# satellitev2.net
KiCad netlist of a schematic drawn in EAGLE
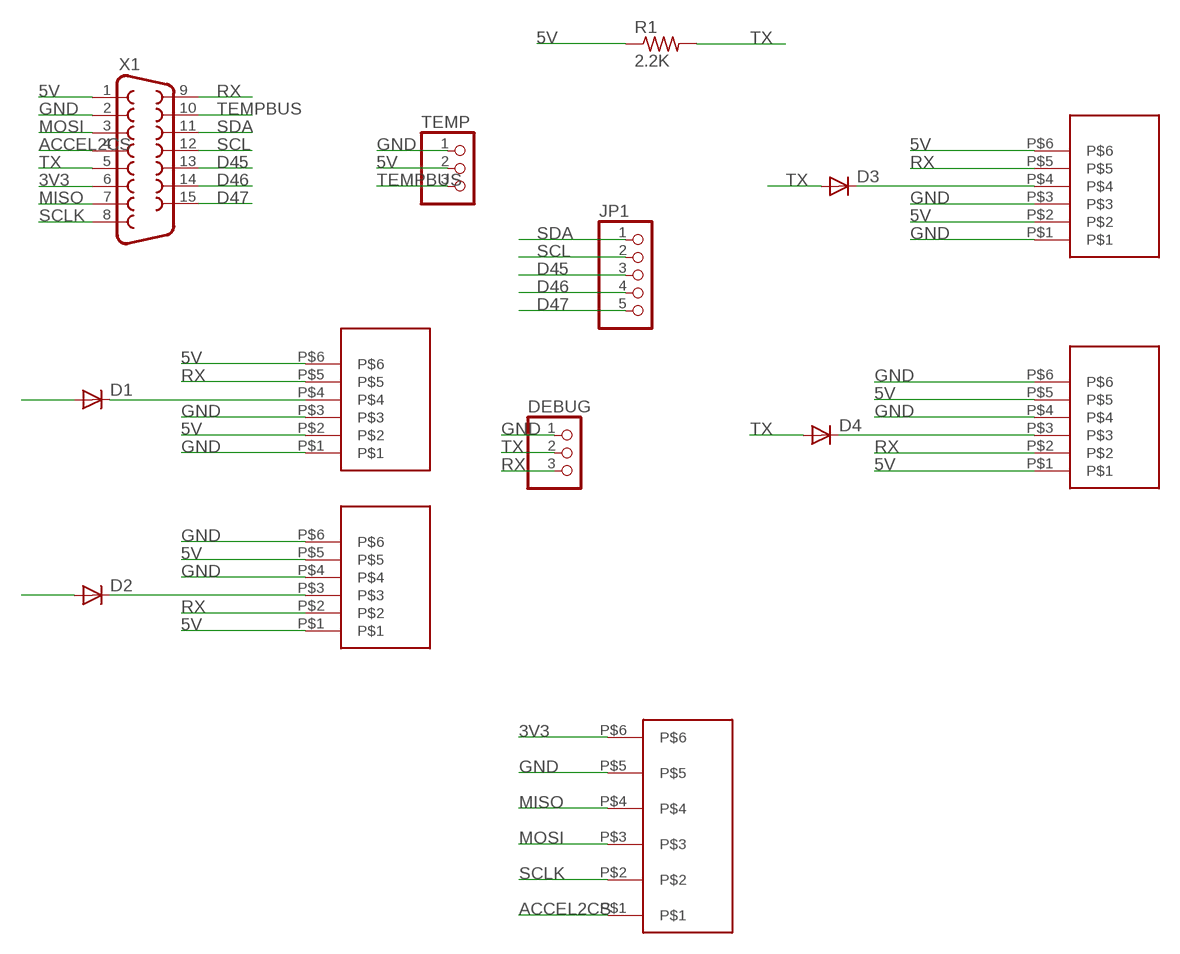
[diagram p0: schematic, sheet 1]

(export (version "E")
  (design (tool "Eeschema 10.0.6"))
  (components
    (comp (ref "D1")
      (value "DIODEPTH")
      (footprint "eagle-import:DIODE-1N4001")
      (libsource (lib "eagle-import") (part "DIODEPTH"))
    )
    (comp (ref "D2")
      (value "DIODEPTH")
      (footprint "eagle-import:DIODE-1N4001")
      (libsource (lib "eagle-import") (part "DIODEPTH"))
    )
    (comp (ref "D3")
      (value "DIODEPTH")
      (footprint "eagle-import:DIODE-1N4001")
      (libsource (lib "eagle-import") (part "DIODEPTH"))
    )
    (comp (ref "D4")
      (value "DIODEPTH")
      (footprint "eagle-import:DIODE-1N4001")
      (libsource (lib "eagle-import") (part "DIODEPTH"))
    )
    (comp (ref "DEBUG")
      (value "PINHD-1X3")
      (footprint "eagle-import:1X03")
      (libsource (lib "eagle-import") (part "PINHD-1X3"))
    )
    (comp (ref "JP1")
      (value "PINHD-1X5")
      (footprint "eagle-import:1X05")
      (libsource (lib "eagle-import") (part "PINHD-1X5"))
    )
    (comp (ref "R1")
      (value "2.2K")
      (footprint "eagle-import:0309_12")
      (libsource (lib "eagle-import") (part "R-US_0309/12"))
    )
    (comp (ref "TEMP")
      (value "PINHD-1X3")
      (footprint "eagle-import:1X03")
      (libsource (lib "eagle-import") (part "PINHD-1X3"))
    )
    (comp (ref "U$1")
      (value "1X6SMDPINS")
      (footprint "eagle-import:1X6SMDPINS")
      (libsource (lib "eagle-import") (part "1X6SMDPINS"))
    )
    (comp (ref "U$2")
      (value "1X6SMDPINS")
      (footprint "eagle-import:1X6SMDPINS")
      (libsource (lib "eagle-import") (part "1X6SMDPINS"))
    )
    (comp (ref "U$3")
      (value "1X6SMDPINSB")
      (footprint "eagle-import:1X6SMDPINSB")
      (libsource (lib "eagle-import") (part "1X6SMDPINSB"))
    )
    (comp (ref "U$4")
      (value "1X6SMDPINSB")
      (footprint "eagle-import:1X6SMDPINSB")
      (libsource (lib "eagle-import") (part "1X6SMDPINSB"))
    )
    (comp (ref "U$5")
      (value "RJ11V")
      (footprint "eagle-import:RJ11V")
      (libsource (lib "eagle-import") (part "RJ11V"))
    )
    (comp (ref "X1")
      (value "F15HDV")
      (footprint "eagle-import:HDF15V")
      (libsource (lib "eagle-import") (part "F15HDV"))
    )
  )
  (nets
    (net (code "1") (name "/3V3") (class "Default")
      (node (ref "U$5") (pin "P$6") (pinfunction "P$6_P$6") (pintype "bidirectional"))
      (node (ref "X1") (pin "6") (pinfunction "6_6") (pintype "passive"))
    )
    (net (code "2") (name "/5V") (class "Default")
      (node (ref "R1") (pin "1") (pinfunction "1_1") (pintype "passive"))
      (node (ref "TEMP") (pin "2") (pinfunction "2_2") (pintype "passive"))
      (node (ref "U$1") (pin "P$2") (pinfunction "P$2_P$2") (pintype "bidirectional"))
      (node (ref "U$1") (pin "P$6") (pinfunction "P$6_P$6") (pintype "bidirectional"))
      (node (ref "U$2") (pin "P$1") (pinfunction "P$1_P$1") (pintype "bidirectional"))
      (node (ref "U$2") (pin "P$5") (pinfunction "P$5_P$5") (pintype "bidirectional"))
      (node (ref "U$3") (pin "P$2") (pinfunction "P$2_P$2") (pintype "bidirectional"))
      (node (ref "U$3") (pin "P$6") (pinfunction "P$6_P$6") (pintype "bidirectional"))
      (node (ref "U$4") (pin "P$1") (pinfunction "P$1_P$1") (pintype "bidirectional"))
      (node (ref "U$4") (pin "P$5") (pinfunction "P$5_P$5") (pintype "bidirectional"))
      (node (ref "X1") (pin "1") (pinfunction "1_1") (pintype "passive"))
    )
    (net (code "3") (name "/ACCEL2CS") (class "Default")
      (node (ref "U$5") (pin "P$1") (pinfunction "P$1_P$1") (pintype "bidirectional"))
      (node (ref "X1") (pin "4") (pinfunction "4_4") (pintype "passive"))
    )
    (net (code "4") (name "/D45") (class "Default")
      (node (ref "JP1") (pin "3") (pinfunction "3_3") (pintype "passive"))
      (node (ref "X1") (pin "13") (pinfunction "13_13") (pintype "passive"))
    )
    (net (code "5") (name "/D46") (class "Default")
      (node (ref "JP1") (pin "4") (pinfunction "4_4") (pintype "passive"))
      (node (ref "X1") (pin "14") (pinfunction "14_14") (pintype "passive"))
    )
    (net (code "6") (name "/D47") (class "Default")
      (node (ref "JP1") (pin "5") (pinfunction "5_5") (pintype "passive"))
      (node (ref "X1") (pin "15") (pinfunction "15_15") (pintype "passive"))
    )
    (net (code "7") (name "/GND") (class "Default")
      (node (ref "DEBUG") (pin "1") (pinfunction "1_1") (pintype "passive"))
      (node (ref "TEMP") (pin "1") (pinfunction "1_1") (pintype "passive"))
      (node (ref "U$1") (pin "P$1") (pinfunction "P$1_P$1") (pintype "bidirectional"))
      (node (ref "U$1") (pin "P$3") (pinfunction "P$3_P$3") (pintype "bidirectional"))
      (node (ref "U$2") (pin "P$4") (pinfunction "P$4_P$4") (pintype "bidirectional"))
      (node (ref "U$2") (pin "P$6") (pinfunction "P$6_P$6") (pintype "bidirectional"))
      (node (ref "U$3") (pin "P$1") (pinfunction "P$1_P$1") (pintype "bidirectional"))
      (node (ref "U$3") (pin "P$3") (pinfunction "P$3_P$3") (pintype "bidirectional"))
      (node (ref "U$4") (pin "P$4") (pinfunction "P$4_P$4") (pintype "bidirectional"))
      (node (ref "U$4") (pin "P$6") (pinfunction "P$6_P$6") (pintype "bidirectional"))
      (node (ref "U$5") (pin "P$5") (pinfunction "P$5_P$5") (pintype "bidirectional"))
      (node (ref "X1") (pin "2") (pinfunction "2_2") (pintype "passive"))
    )
    (net (code "8") (name "/MISO") (class "Default")
      (node (ref "U$5") (pin "P$4") (pinfunction "P$4_P$4") (pintype "bidirectional"))
      (node (ref "X1") (pin "7") (pinfunction "7_7") (pintype "passive"))
    )
    (net (code "9") (name "/MOSI") (class "Default")
      (node (ref "U$5") (pin "P$3") (pinfunction "P$3_P$3") (pintype "bidirectional"))
      (node (ref "X1") (pin "3") (pinfunction "3_3") (pintype "passive"))
    )
    (net (code "10") (name "/RX") (class "Default")
      (node (ref "DEBUG") (pin "3") (pinfunction "3_3") (pintype "passive"))
      (node (ref "U$1") (pin "P$5") (pinfunction "P$5_P$5") (pintype "bidirectional"))
      (node (ref "U$2") (pin "P$2") (pinfunction "P$2_P$2") (pintype "bidirectional"))
      (node (ref "U$3") (pin "P$5") (pinfunction "P$5_P$5") (pintype "bidirectional"))
      (node (ref "U$4") (pin "P$2") (pinfunction "P$2_P$2") (pintype "bidirectional"))
      (node (ref "X1") (pin "9") (pinfunction "9_9") (pintype "passive"))
    )
    (net (code "11") (name "/SCL") (class "Default")
      (node (ref "JP1") (pin "2") (pinfunction "2_2") (pintype "passive"))
      (node (ref "X1") (pin "12") (pinfunction "12_12") (pintype "passive"))
    )
    (net (code "12") (name "/SCLK") (class "Default")
      (node (ref "U$5") (pin "P$2") (pinfunction "P$2_P$2") (pintype "bidirectional"))
      (node (ref "X1") (pin "8") (pinfunction "8_8") (pintype "passive"))
    )
    (net (code "13") (name "/SDA") (class "Default")
      (node (ref "JP1") (pin "1") (pinfunction "1_1") (pintype "passive"))
      (node (ref "X1") (pin "11") (pinfunction "11_11") (pintype "passive"))
    )
    (net (code "14") (name "/TEMPBUS") (class "Default")
      (node (ref "TEMP") (pin "3") (pinfunction "3_3") (pintype "passive"))
      (node (ref "X1") (pin "10") (pinfunction "10_10") (pintype "passive"))
    )
    (net (code "15") (name "/TX") (class "Default")
      (node (ref "D1") (pin "A") (pinfunction "A_A") (pintype "passive"))
      (node (ref "D2") (pin "A") (pinfunction "A_A") (pintype "passive"))
      (node (ref "D3") (pin "A") (pinfunction "A_A") (pintype "passive"))
      (node (ref "D4") (pin "A") (pinfunction "A_A") (pintype "passive"))
      (node (ref "DEBUG") (pin "2") (pinfunction "2_2") (pintype "passive"))
      (node (ref "R1") (pin "2") (pinfunction "2_2") (pintype "passive"))
      (node (ref "X1") (pin "5") (pinfunction "5_5") (pintype "passive"))
    )
    (net (code "16") (name "Net-(D1-PadC)") (class "Default")
      (node (ref "D1") (pin "C") (pinfunction "C_C") (pintype "passive"))
      (node (ref "U$1") (pin "P$4") (pinfunction "P$4_P$4") (pintype "bidirectional"))
    )
    (net (code "17") (name "Net-(D2-PadC)") (class "Default")
      (node (ref "D2") (pin "C") (pinfunction "C_C") (pintype "passive"))
      (node (ref "U$2") (pin "P$3") (pinfunction "P$3_P$3") (pintype "bidirectional"))
    )
    (net (code "18") (name "Net-(D3-PadC)") (class "Default")
      (node (ref "D3") (pin "C") (pinfunction "C_C") (pintype "passive"))
      (node (ref "U$3") (pin "P$4") (pinfunction "P$4_P$4") (pintype "bidirectional"))
    )
    (net (code "19") (name "Net-(D4-PadC)") (class "Default")
      (node (ref "D4") (pin "C") (pinfunction "C_C") (pintype "passive"))
      (node (ref "U$4") (pin "P$3") (pinfunction "P$3_P$3") (pintype "bidirectional"))
    )
  )
)
